# MotorDriver.net
KiCad netlist of a schematic drawn in Altium Designer
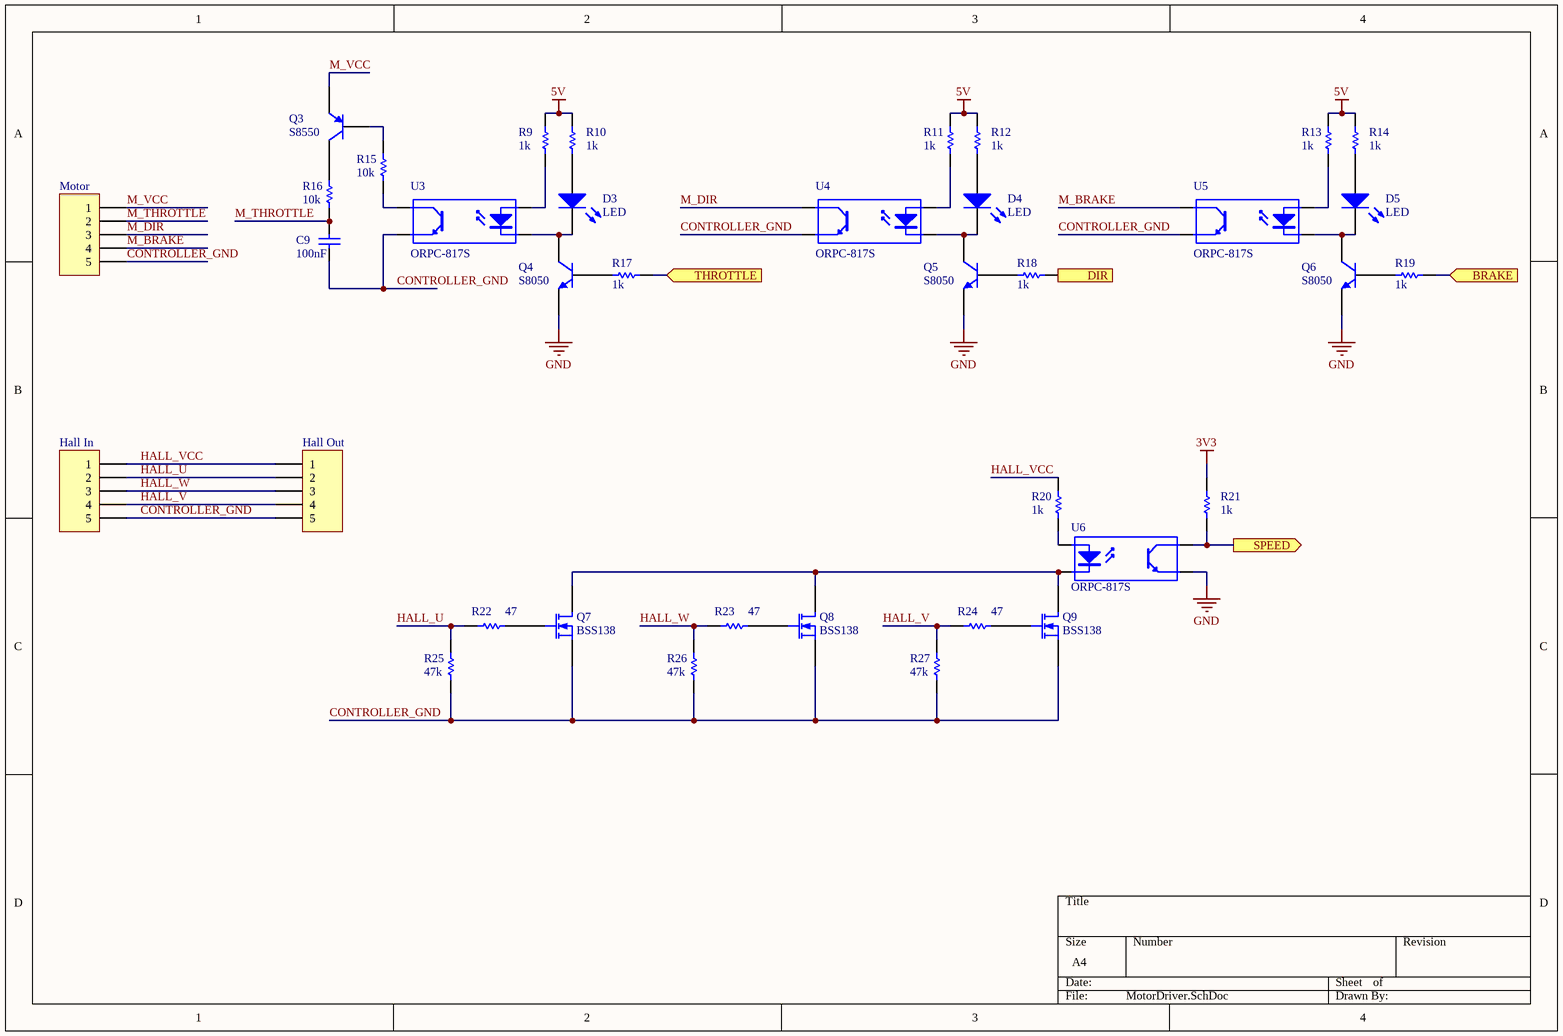
[diagram p0: MotorDriver.SchDoc]

(export (version "E")
  (design (tool "Eeschema 10.0.6"))
  (components
    (comp (ref "C9")
      (value "100nF")
      (footprint "J1-0603")
      (description "Capacitor")
      (fields (field (name "Comment") "Cap") (field (name "PUBLISHER") "Altium Limited"))
      (libsource (lib "Miscellaneous Devices") (part "Cap"))
    )
    (comp (ref "D3")
      (value "LED")
      (footprint "J1-0603 LED")
      (fields (field (name "PUBLISHER") "Altium Limited"))
      (libsource (lib "sumo") (part "LED"))
    )
    (comp (ref "D4")
      (value "LED")
      (footprint "J1-0603 LED")
      (fields (field (name "PUBLISHER") "Altium Limited"))
      (libsource (lib "sumo") (part "LED"))
    )
    (comp (ref "D5")
      (value "LED")
      (footprint "J1-0603 LED")
      (fields (field (name "PUBLISHER") "Altium Limited"))
      (libsource (lib "sumo") (part "LED"))
    )
    (comp (ref "Hall In")
      (value "Motor 1")
      (footprint "HDR1X5")
      (description "Control Signals from a E-Bike controller")
      (fields (field (name "PUBLISHER") "Altium Limited"))
      (libsource (lib "Miscellaneous Connectors") (part "Header 5"))
    )
    (comp (ref "Hall Out")
      (value "Motor 1")
      (footprint "HDR1X5")
      (description "Control Signals from a E-Bike controller")
      (fields (field (name "PUBLISHER") "Altium Limited"))
      (libsource (lib "") (part "Header 5_1"))
    )
    (comp (ref "Motor")
      (value "Motor 1")
      (footprint "HDR1X5")
      (description "Control Signals from a E-Bike controller")
      (fields (field (name "PUBLISHER") "Altium Limited"))
      (libsource (lib "Miscellaneous Connectors") (part "Header 5"))
    )
    (comp (ref "Q3")
      (value "S8550")
      (footprint "SOT23-3M")
      (description "PNP General Purpose Amplifier")
      (fields (field (name "PUBLISHER") "Altium Limited"))
      (libsource (lib "sumo") (part "S8550"))
    )
    (comp (ref "Q4")
      (value "S8050")
      (footprint "SOT23-3M")
      (description "NPN General Purpose Amplifier")
      (fields (field (name "PUBLISHER") "Altium Limited"))
      (libsource (lib "sumo") (part "S8050"))
    )
    (comp (ref "Q5")
      (value "S8050")
      (footprint "SOT23-3M")
      (description "NPN General Purpose Amplifier")
      (fields (field (name "PUBLISHER") "Altium Limited"))
      (libsource (lib "sumo") (part "S8050"))
    )
    (comp (ref "Q6")
      (value "S8050")
      (footprint "SOT23-3M")
      (description "NPN General Purpose Amplifier")
      (fields (field (name "PUBLISHER") "Altium Limited"))
      (libsource (lib "sumo") (part "S8050"))
    )
    (comp (ref "Q7")
      (value "BSS138")
      (footprint "SOT23-3M")
      (description "N-Channel MOSFET")
      (fields (field (name "PUBLISHER") "Altium Limited"))
      (libsource (lib "sumo") (part "BSS138"))
    )
    (comp (ref "Q8")
      (value "BSS138")
      (footprint "SOT23-3M")
      (description "N-Channel MOSFET")
      (fields (field (name "PUBLISHER") "Altium Limited"))
      (libsource (lib "sumo") (part "BSS138"))
    )
    (comp (ref "Q9")
      (value "BSS138")
      (footprint "SOT23-3M")
      (description "N-Channel MOSFET")
      (fields (field (name "PUBLISHER") "Altium Limited"))
      (libsource (lib "sumo") (part "BSS138"))
    )
    (comp (ref "R9")
      (value "1k")
      (footprint "J1-0603")
      (description "Resistor")
      (fields (field (name "Comment") "Res1") (field (name "PUBLISHER") "Altium Limited"))
      (libsource (lib "Miscellaneous Devices") (part "Res1"))
    )
    (comp (ref "R10")
      (value "1k")
      (footprint "J1-0603")
      (description "Resistor")
      (fields (field (name "Comment") "Res1") (field (name "PUBLISHER") "Altium Limited"))
      (libsource (lib "Miscellaneous Devices") (part "Res1"))
    )
    (comp (ref "R11")
      (value "1k")
      (footprint "J1-0603")
      (description "Resistor")
      (fields (field (name "Comment") "Res1") (field (name "PUBLISHER") "Altium Limited"))
      (libsource (lib "Miscellaneous Devices") (part "Res1"))
    )
    (comp (ref "R12")
      (value "1k")
      (footprint "J1-0603")
      (description "Resistor")
      (fields (field (name "Comment") "Res1") (field (name "PUBLISHER") "Altium Limited"))
      (libsource (lib "Miscellaneous Devices") (part "Res1"))
    )
    (comp (ref "R13")
      (value "1k")
      (footprint "J1-0603")
      (description "Resistor")
      (fields (field (name "Comment") "Res1") (field (name "PUBLISHER") "Altium Limited"))
      (libsource (lib "Miscellaneous Devices") (part "Res1"))
    )
    (comp (ref "R14")
      (value "1k")
      (footprint "J1-0603")
      (description "Resistor")
      (fields (field (name "Comment") "Res1") (field (name "PUBLISHER") "Altium Limited"))
      (libsource (lib "Miscellaneous Devices") (part "Res1"))
    )
    (comp (ref "R15")
      (value "10k")
      (footprint "J1-0603")
      (description "Resistor")
      (fields (field (name "Comment") "Res1") (field (name "PUBLISHER") "Altium Limited"))
      (libsource (lib "Miscellaneous Devices") (part "Res1"))
    )
    (comp (ref "R16")
      (value "10k")
      (footprint "J1-0603")
      (description "Resistor")
      (fields (field (name "Comment") "Res1") (field (name "PUBLISHER") "Altium Limited"))
      (libsource (lib "Miscellaneous Devices") (part "Res1"))
    )
    (comp (ref "R17")
      (value "1k")
      (footprint "J1-0603")
      (description "Resistor")
      (fields (field (name "Comment") "Res1") (field (name "PUBLISHER") "Altium Limited"))
      (libsource (lib "Miscellaneous Devices") (part "Res1"))
    )
    (comp (ref "R18")
      (value "1k")
      (footprint "J1-0603")
      (description "Resistor")
      (fields (field (name "Comment") "Res1") (field (name "PUBLISHER") "Altium Limited"))
      (libsource (lib "Miscellaneous Devices") (part "Res1"))
    )
    (comp (ref "R19")
      (value "1k")
      (footprint "J1-0603")
      (description "Resistor")
      (fields (field (name "Comment") "Res1") (field (name "PUBLISHER") "Altium Limited"))
      (libsource (lib "Miscellaneous Devices") (part "Res1"))
    )
    (comp (ref "R20")
      (value "1k")
      (footprint "J1-0603")
      (description "Resistor")
      (fields (field (name "Comment") "Res1") (field (name "PUBLISHER") "Altium Limited"))
      (libsource (lib "Miscellaneous Devices") (part "Res1"))
    )
    (comp (ref "R21")
      (value "1k")
      (footprint "J1-0603")
      (description "Resistor")
      (fields (field (name "Comment") "Res1") (field (name "PUBLISHER") "Altium Limited"))
      (libsource (lib "Miscellaneous Devices") (part "Res1"))
    )
    (comp (ref "R22")
      (value "47")
      (footprint "J1-0603")
      (description "Resistor")
      (fields (field (name "Comment") "Res1") (field (name "PUBLISHER") "Altium Limited"))
      (libsource (lib "Miscellaneous Devices") (part "Res1"))
    )
    (comp (ref "R23")
      (value "47")
      (footprint "J1-0603")
      (description "Resistor")
      (fields (field (name "Comment") "Res1") (field (name "PUBLISHER") "Altium Limited"))
      (libsource (lib "Miscellaneous Devices") (part "Res1"))
    )
    (comp (ref "R24")
      (value "47")
      (footprint "J1-0603")
      (description "Resistor")
      (fields (field (name "Comment") "Res1") (field (name "PUBLISHER") "Altium Limited"))
      (libsource (lib "Miscellaneous Devices") (part "Res1"))
    )
    (comp (ref "R25")
      (value "47k")
      (footprint "J1-0603")
      (description "Resistor")
      (fields (field (name "Comment") "Res1") (field (name "PUBLISHER") "Altium Limited"))
      (libsource (lib "Miscellaneous Devices") (part "Res1"))
    )
    (comp (ref "R26")
      (value "47k")
      (footprint "J1-0603")
      (description "Resistor")
      (fields (field (name "Comment") "Res1") (field (name "PUBLISHER") "Altium Limited"))
      (libsource (lib "Miscellaneous Devices") (part "Res1"))
    )
    (comp (ref "R27")
      (value "47k")
      (footprint "J1-0603")
      (description "Resistor")
      (fields (field (name "Comment") "Res1") (field (name "PUBLISHER") "Altium Limited"))
      (libsource (lib "Miscellaneous Devices") (part "Res1"))
    )
    (comp (ref "U3")
      (value "ORPC-817S")
      (footprint "SMD-4")
      (description "4-Pin Phototransistor Optocoupler")
      (fields (field (name "PUBLISHER") "Altium Limited"))
      (libsource (lib "sumo") (part "ORPC-817S"))
    )
    (comp (ref "U4")
      (value "ORPC-817S")
      (footprint "SMD-4")
      (description "4-Pin Phototransistor Optocoupler")
      (fields (field (name "PUBLISHER") "Altium Limited"))
      (libsource (lib "sumo") (part "ORPC-817S"))
    )
    (comp (ref "U5")
      (value "ORPC-817S")
      (footprint "SMD-4")
      (description "4-Pin Phototransistor Optocoupler")
      (fields (field (name "PUBLISHER") "Altium Limited"))
      (libsource (lib "sumo") (part "ORPC-817S"))
    )
    (comp (ref "U6")
      (value "ORPC-817S")
      (footprint "SMD-4")
      (description "4-Pin Phototransistor Optocoupler")
      (fields (field (name "PUBLISHER") "Altium Limited"))
      (libsource (lib "sumo") (part "ORPC-817S"))
    )
  )
  (nets
    (net (code "1") (name "/BRAKE") (class "Default")
      (node (ref "R19") (pin "1") (pinfunction "1_1") (pintype "passive"))
    )
    (net (code "2") (name "/CONTROLLER_GND") (class "Default")
      (node (ref "C9") (pin "1") (pinfunction "1_1") (pintype "passive"))
      (node (ref "Hall In") (pin "5") (pinfunction "5_5") (pintype "passive"))
      (node (ref "Hall Out") (pin "5") (pinfunction "5_5") (pintype "passive"))
      (node (ref "Motor") (pin "5") (pinfunction "5_5") (pintype "passive"))
      (node (ref "Q7") (pin "2") (pinfunction "S_2") (pintype "passive"))
      (node (ref "Q8") (pin "2") (pinfunction "S_2") (pintype "passive"))
      (node (ref "Q9") (pin "2") (pinfunction "S_2") (pintype "passive"))
      (node (ref "R25") (pin "1") (pinfunction "1_1") (pintype "passive"))
      (node (ref "R26") (pin "1") (pinfunction "1_1") (pintype "passive"))
      (node (ref "R27") (pin "1") (pinfunction "1_1") (pintype "passive"))
      (node (ref "U3") (pin "3") (pinfunction "E_3") (pintype "passive"))
      (node (ref "U4") (pin "3") (pinfunction "E_3") (pintype "passive"))
      (node (ref "U5") (pin "3") (pinfunction "E_3") (pintype "passive"))
    )
    (net (code "3") (name "/DIR") (class "Default")
      (node (ref "R18") (pin "1") (pinfunction "1_1") (pintype "passive"))
    )
    (net (code "4") (name "/HALL_U") (class "Default")
      (node (ref "Hall In") (pin "2") (pinfunction "2_2") (pintype "passive"))
      (node (ref "Hall Out") (pin "2") (pinfunction "2_2") (pintype "passive"))
      (node (ref "R22") (pin "2") (pinfunction "2_2") (pintype "passive"))
      (node (ref "R25") (pin "2") (pinfunction "2_2") (pintype "passive"))
    )
    (net (code "5") (name "/HALL_V") (class "Default")
      (node (ref "Hall In") (pin "4") (pinfunction "4_4") (pintype "passive"))
      (node (ref "Hall Out") (pin "4") (pinfunction "4_4") (pintype "passive"))
      (node (ref "R24") (pin "2") (pinfunction "2_2") (pintype "passive"))
      (node (ref "R27") (pin "2") (pinfunction "2_2") (pintype "passive"))
    )
    (net (code "6") (name "/HALL_VCC") (class "Default")
      (node (ref "Hall In") (pin "1") (pinfunction "1_1") (pintype "passive"))
      (node (ref "Hall Out") (pin "1") (pinfunction "1_1") (pintype "passive"))
      (node (ref "R20") (pin "2") (pinfunction "2_2") (pintype "passive"))
    )
    (net (code "7") (name "/HALL_W") (class "Default")
      (node (ref "Hall In") (pin "3") (pinfunction "3_3") (pintype "passive"))
      (node (ref "Hall Out") (pin "3") (pinfunction "3_3") (pintype "passive"))
      (node (ref "R23") (pin "2") (pinfunction "2_2") (pintype "passive"))
      (node (ref "R26") (pin "2") (pinfunction "2_2") (pintype "passive"))
    )
    (net (code "8") (name "/M_BRAKE") (class "Default")
      (node (ref "Motor") (pin "4") (pinfunction "4_4") (pintype "passive"))
      (node (ref "U5") (pin "4") (pinfunction "C_4") (pintype "passive"))
    )
    (net (code "9") (name "/M_DIR") (class "Default")
      (node (ref "Motor") (pin "3") (pinfunction "3_3") (pintype "passive"))
      (node (ref "U4") (pin "4") (pinfunction "C_4") (pintype "passive"))
    )
    (net (code "10") (name "/M_THROTTLE") (class "Default")
      (node (ref "C9") (pin "2") (pinfunction "2_2") (pintype "passive"))
      (node (ref "Motor") (pin "2") (pinfunction "2_2") (pintype "passive"))
      (node (ref "R16") (pin "1") (pinfunction "1_1") (pintype "passive"))
    )
    (net (code "11") (name "/M_VCC") (class "Default")
      (node (ref "Motor") (pin "1") (pinfunction "1_1") (pintype "passive"))
      (node (ref "Q3") (pin "2") (pinfunction "E_2") (pintype "passive"))
    )
    (net (code "12") (name "/SPEED") (class "Default")
      (node (ref "R21") (pin "1") (pinfunction "1_1") (pintype "passive"))
      (node (ref "U6") (pin "4") (pinfunction "C_4") (pintype "passive"))
    )
    (net (code "13") (name "/THROTTLE") (class "Default")
      (node (ref "R17") (pin "1") (pinfunction "1_1") (pintype "passive"))
    )
    (net (code "14") (name "3V3") (class "Default")
      (node (ref "R21") (pin "2") (pinfunction "2_2") (pintype "passive"))
    )
    (net (code "15") (name "5V") (class "Default")
      (node (ref "R10") (pin "2") (pinfunction "2_2") (pintype "passive"))
      (node (ref "R11") (pin "2") (pinfunction "2_2") (pintype "passive"))
      (node (ref "R12") (pin "2") (pinfunction "2_2") (pintype "passive"))
      (node (ref "R13") (pin "2") (pinfunction "2_2") (pintype "passive"))
      (node (ref "R14") (pin "2") (pinfunction "2_2") (pintype "passive"))
      (node (ref "R9") (pin "2") (pinfunction "2_2") (pintype "passive"))
    )
    (net (code "16") (name "GND") (class "Default")
      (node (ref "Q4") (pin "2") (pinfunction "E_2") (pintype "passive"))
      (node (ref "Q5") (pin "2") (pinfunction "E_2") (pintype "passive"))
      (node (ref "Q6") (pin "2") (pinfunction "E_2") (pintype "passive"))
      (node (ref "U6") (pin "3") (pinfunction "E_3") (pintype "passive"))
    )
    (net (code "17") (name "Net-(D3-A)") (class "Default")
      (node (ref "D3") (pin "1") (pinfunction "A_1") (pintype "passive"))
      (node (ref "R10") (pin "1") (pinfunction "1_1") (pintype "passive"))
    )
    (net (code "18") (name "Net-(D3-K)") (class "Default")
      (node (ref "D3") (pin "2") (pinfunction "K_2") (pintype "passive"))
      (node (ref "Q4") (pin "3") (pinfunction "C_3") (pintype "passive"))
      (node (ref "U3") (pin "2") (pinfunction "K_2") (pintype "passive"))
    )
    (net (code "19") (name "Net-(D4-A)") (class "Default")
      (node (ref "D4") (pin "1") (pinfunction "A_1") (pintype "passive"))
      (node (ref "R12") (pin "1") (pinfunction "1_1") (pintype "passive"))
    )
    (net (code "20") (name "Net-(D4-K)") (class "Default")
      (node (ref "D4") (pin "2") (pinfunction "K_2") (pintype "passive"))
      (node (ref "Q5") (pin "3") (pinfunction "C_3") (pintype "passive"))
      (node (ref "U4") (pin "2") (pinfunction "K_2") (pintype "passive"))
    )
    (net (code "21") (name "Net-(D5-A)") (class "Default")
      (node (ref "D5") (pin "1") (pinfunction "A_1") (pintype "passive"))
      (node (ref "R14") (pin "1") (pinfunction "1_1") (pintype "passive"))
    )
    (net (code "22") (name "Net-(D5-K)") (class "Default")
      (node (ref "D5") (pin "2") (pinfunction "K_2") (pintype "passive"))
      (node (ref "Q6") (pin "3") (pinfunction "C_3") (pintype "passive"))
      (node (ref "U5") (pin "2") (pinfunction "K_2") (pintype "passive"))
    )
    (net (code "23") (name "Net-(Q3-B)") (class "Default")
      (node (ref "Q3") (pin "1") (pinfunction "B_1") (pintype "passive"))
      (node (ref "R15") (pin "2") (pinfunction "2_2") (pintype "passive"))
    )
    (net (code "24") (name "Net-(Q3-C)") (class "Default")
      (node (ref "Q3") (pin "3") (pinfunction "C_3") (pintype "passive"))
      (node (ref "R16") (pin "2") (pinfunction "2_2") (pintype "passive"))
    )
    (net (code "25") (name "Net-(Q4-B)") (class "Default")
      (node (ref "Q4") (pin "1") (pinfunction "B_1") (pintype "passive"))
      (node (ref "R17") (pin "2") (pinfunction "2_2") (pintype "passive"))
    )
    (net (code "26") (name "Net-(Q5-B)") (class "Default")
      (node (ref "Q5") (pin "1") (pinfunction "B_1") (pintype "passive"))
      (node (ref "R18") (pin "2") (pinfunction "2_2") (pintype "passive"))
    )
    (net (code "27") (name "Net-(Q6-B)") (class "Default")
      (node (ref "Q6") (pin "1") (pinfunction "B_1") (pintype "passive"))
      (node (ref "R19") (pin "2") (pinfunction "2_2") (pintype "passive"))
    )
    (net (code "28") (name "Net-(Q7-D)") (class "Default")
      (node (ref "Q7") (pin "3") (pinfunction "D_3") (pintype "passive"))
      (node (ref "Q8") (pin "3") (pinfunction "D_3") (pintype "passive"))
      (node (ref "Q9") (pin "3") (pinfunction "D_3") (pintype "passive"))
      (node (ref "U6") (pin "2") (pinfunction "K_2") (pintype "passive"))
    )
    (net (code "29") (name "Net-(Q7-G)") (class "Default")
      (node (ref "Q7") (pin "1") (pinfunction "G_1") (pintype "passive"))
      (node (ref "R22") (pin "1") (pinfunction "1_1") (pintype "passive"))
    )
    (net (code "30") (name "Net-(Q8-G)") (class "Default")
      (node (ref "Q8") (pin "1") (pinfunction "G_1") (pintype "passive"))
      (node (ref "R23") (pin "1") (pinfunction "1_1") (pintype "passive"))
    )
    (net (code "31") (name "Net-(Q9-G)") (class "Default")
      (node (ref "Q9") (pin "1") (pinfunction "G_1") (pintype "passive"))
      (node (ref "R24") (pin "1") (pinfunction "1_1") (pintype "passive"))
    )
    (net (code "32") (name "Net-(U3-A)") (class "Default")
      (node (ref "R9") (pin "1") (pinfunction "1_1") (pintype "passive"))
      (node (ref "U3") (pin "1") (pinfunction "A_1") (pintype "passive"))
    )
    (net (code "33") (name "Net-(U3-C)") (class "Default")
      (node (ref "R15") (pin "1") (pinfunction "1_1") (pintype "passive"))
      (node (ref "U3") (pin "4") (pinfunction "C_4") (pintype "passive"))
    )
    (net (code "34") (name "Net-(U4-A)") (class "Default")
      (node (ref "R11") (pin "1") (pinfunction "1_1") (pintype "passive"))
      (node (ref "U4") (pin "1") (pinfunction "A_1") (pintype "passive"))
    )
    (net (code "35") (name "Net-(U5-A)") (class "Default")
      (node (ref "R13") (pin "1") (pinfunction "1_1") (pintype "passive"))
      (node (ref "U5") (pin "1") (pinfunction "A_1") (pintype "passive"))
    )
    (net (code "36") (name "Net-(U6-A)") (class "Default")
      (node (ref "R20") (pin "1") (pinfunction "1_1") (pintype "passive"))
      (node (ref "U6") (pin "1") (pinfunction "A_1") (pintype "passive"))
    )
  )
)
